# Connectors.net
KiCad netlist of a schematic drawn in Altium Designer
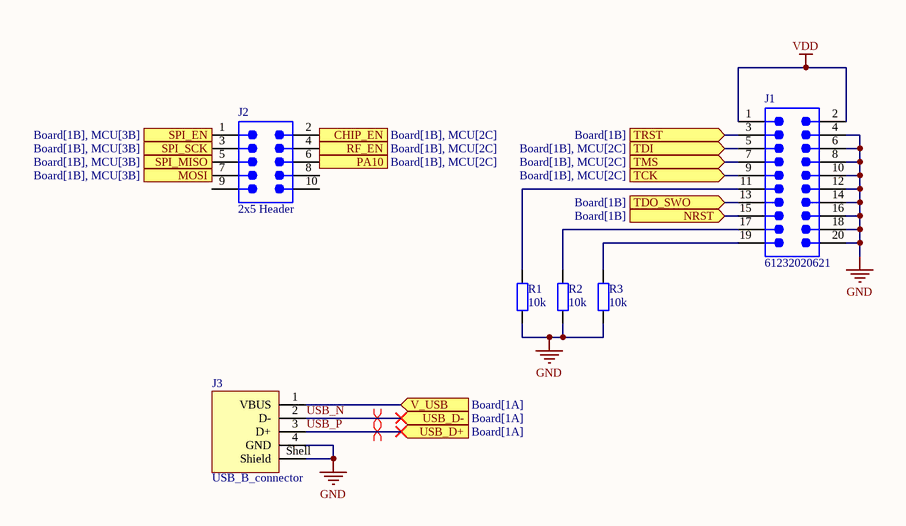
[diagram p0: Connectors.SchDoc]

(export (version "E")
  (design (tool "Eeschema 10.0.6"))
  (components
    (comp (ref "J1")
      (value "61232020621")
      (footprint "61232020621")
      (libsource (lib "schematics") (part "2x10 JTAG"))
    )
    (comp (ref "J2")
      (value "2x5 Header")
      (footprint "SMTC-MMT-105-01-X-DH")
      (description "Horizontal Surface Mount Header, -55 to 125 degC, 2 mm Pitch, 10-Pin, Male, RoHS")
      (fields (field (name "PARTNUMBER") "MMT-105-01-F-DH") (field (name "MANUFACTURER") "Samtec"))
      (libsource (lib "schematics") (part "2x5 Header"))
    )
    (comp (ref "J3")
      (value "USB_B_connector")
      (footprint "62910416121")
      (libsource (lib "schematics") (part "USB_B_connector"))
    )
    (comp (ref "R1") (value "10k") (footprint "Res_0402") (libsource (lib "schematics") (part "Resistor_EU")))
    (comp (ref "R2") (value "10k") (footprint "Res_0402") (libsource (lib "schematics") (part "Resistor_EU")))
    (comp (ref "R3") (value "10k") (footprint "Res_0402") (libsource (lib "schematics") (part "Resistor_EU")))
  )
  (nets
    (net (code "1") (name "/CHIP_EN") (class "Default")
      (node (ref "J2") (pin "2") (pinfunction "2_2") (pintype "passive"))
    )
    (net (code "2") (name "/MOSI") (class "Default")
      (node (ref "J2") (pin "7") (pinfunction "7_7") (pintype "passive"))
    )
    (net (code "3") (name "/NRST") (class "Default")
      (node (ref "J1") (pin "15") (pinfunction "15_15") (pintype "passive"))
    )
    (net (code "4") (name "/PA10") (class "Default")
      (node (ref "J2") (pin "6") (pinfunction "6_6") (pintype "passive"))
    )
    (net (code "5") (name "/RF_EN") (class "Default")
      (node (ref "J2") (pin "4") (pinfunction "4_4") (pintype "passive"))
    )
    (net (code "6") (name "/SPI_EN") (class "Default")
      (node (ref "J2") (pin "1") (pinfunction "1_1") (pintype "passive"))
    )
    (net (code "7") (name "/SPI_MISO") (class "Default")
      (node (ref "J2") (pin "5") (pinfunction "5_5") (pintype "passive"))
    )
    (net (code "8") (name "/SPI_SCK") (class "Default")
      (node (ref "J2") (pin "3") (pinfunction "3_3") (pintype "passive"))
    )
    (net (code "9") (name "/TCK") (class "Default")
      (node (ref "J1") (pin "9") (pinfunction "9_9") (pintype "passive"))
    )
    (net (code "10") (name "/TDI") (class "Default")
      (node (ref "J1") (pin "5") (pinfunction "5_5") (pintype "passive"))
    )
    (net (code "11") (name "/TDO_SWO") (class "Default")
      (node (ref "J1") (pin "13") (pinfunction "13_13") (pintype "passive"))
    )
    (net (code "12") (name "/TMS") (class "Default")
      (node (ref "J1") (pin "7") (pinfunction "7_7") (pintype "passive"))
    )
    (net (code "13") (name "/TRST") (class "Default")
      (node (ref "J1") (pin "3") (pinfunction "3_3") (pintype "passive"))
    )
    (net (code "14") (name "/USB_N") (class "Default")
      (node (ref "J3") (pin "2") (pinfunction "D-_2") (pintype "passive+no_connect"))
    )
    (net (code "15") (name "/USB_P") (class "Default")
      (node (ref "J3") (pin "3") (pinfunction "D+_3") (pintype "passive+no_connect"))
    )
    (net (code "16") (name "/V_USB") (class "Default")
      (node (ref "J3") (pin "1") (pinfunction "VBUS_1") (pintype "passive"))
    )
    (net (code "17") (name "GND") (class "Default")
      (node (ref "J1") (pin "10") (pinfunction "10_10") (pintype "passive"))
      (node (ref "J1") (pin "12") (pinfunction "12_12") (pintype "passive"))
      (node (ref "J1") (pin "14") (pinfunction "14_14") (pintype "passive"))
      (node (ref "J1") (pin "16") (pinfunction "16_16") (pintype "passive"))
      (node (ref "J1") (pin "18") (pinfunction "18_18") (pintype "passive"))
      (node (ref "J1") (pin "20") (pinfunction "20_20") (pintype "passive"))
      (node (ref "J1") (pin "4") (pinfunction "4_4") (pintype "passive"))
      (node (ref "J1") (pin "6") (pinfunction "6_6") (pintype "passive"))
      (node (ref "J1") (pin "8") (pinfunction "8_8") (pintype "passive"))
      (node (ref "J3") (pin "4") (pinfunction "GND_4") (pintype "passive"))
      (node (ref "J3") (pin "Shell") (pinfunction "Shield_Shell") (pintype "passive"))
      (node (ref "R1") (pin "1") (pinfunction "1_1") (pintype "passive"))
      (node (ref "R2") (pin "1") (pinfunction "1_1") (pintype "passive"))
      (node (ref "R3") (pin "1") (pinfunction "1_1") (pintype "passive"))
    )
    (net (code "18") (name "Net-(J1-Pad11)") (class "Default")
      (node (ref "J1") (pin "11") (pinfunction "11_11") (pintype "passive"))
      (node (ref "R1") (pin "2") (pinfunction "2_2") (pintype "passive"))
    )
    (net (code "19") (name "Net-(J1-Pad17)") (class "Default")
      (node (ref "J1") (pin "17") (pinfunction "17_17") (pintype "passive"))
      (node (ref "R2") (pin "2") (pinfunction "2_2") (pintype "passive"))
    )
    (net (code "20") (name "Net-(J1-Pad19)") (class "Default")
      (node (ref "J1") (pin "19") (pinfunction "19_19") (pintype "passive"))
      (node (ref "R3") (pin "2") (pinfunction "2_2") (pintype "passive"))
    )
    (net (code "21") (name "VDD") (class "Default")
      (node (ref "J1") (pin "1") (pinfunction "1_1") (pintype "passive"))
      (node (ref "J1") (pin "2") (pinfunction "2_2") (pintype "passive"))
    )
    (net (code "22") (name "unconnected-(J2-Pad8)") (class "Default")
      (node (ref "J2") (pin "8") (pinfunction "8_8") (pintype "passive"))
    )
    (net (code "23") (name "unconnected-(J2-Pad9)") (class "Default")
      (node (ref "J2") (pin "9") (pinfunction "9_9") (pintype "passive"))
    )
    (net (code "24") (name "unconnected-(J2-Pad10)") (class "Default")
      (node (ref "J2") (pin "10") (pinfunction "10_10") (pintype "passive"))
    )
  )
)
